# Schematic_V1.net
KiCad netlist of a schematic drawn in EAGLE
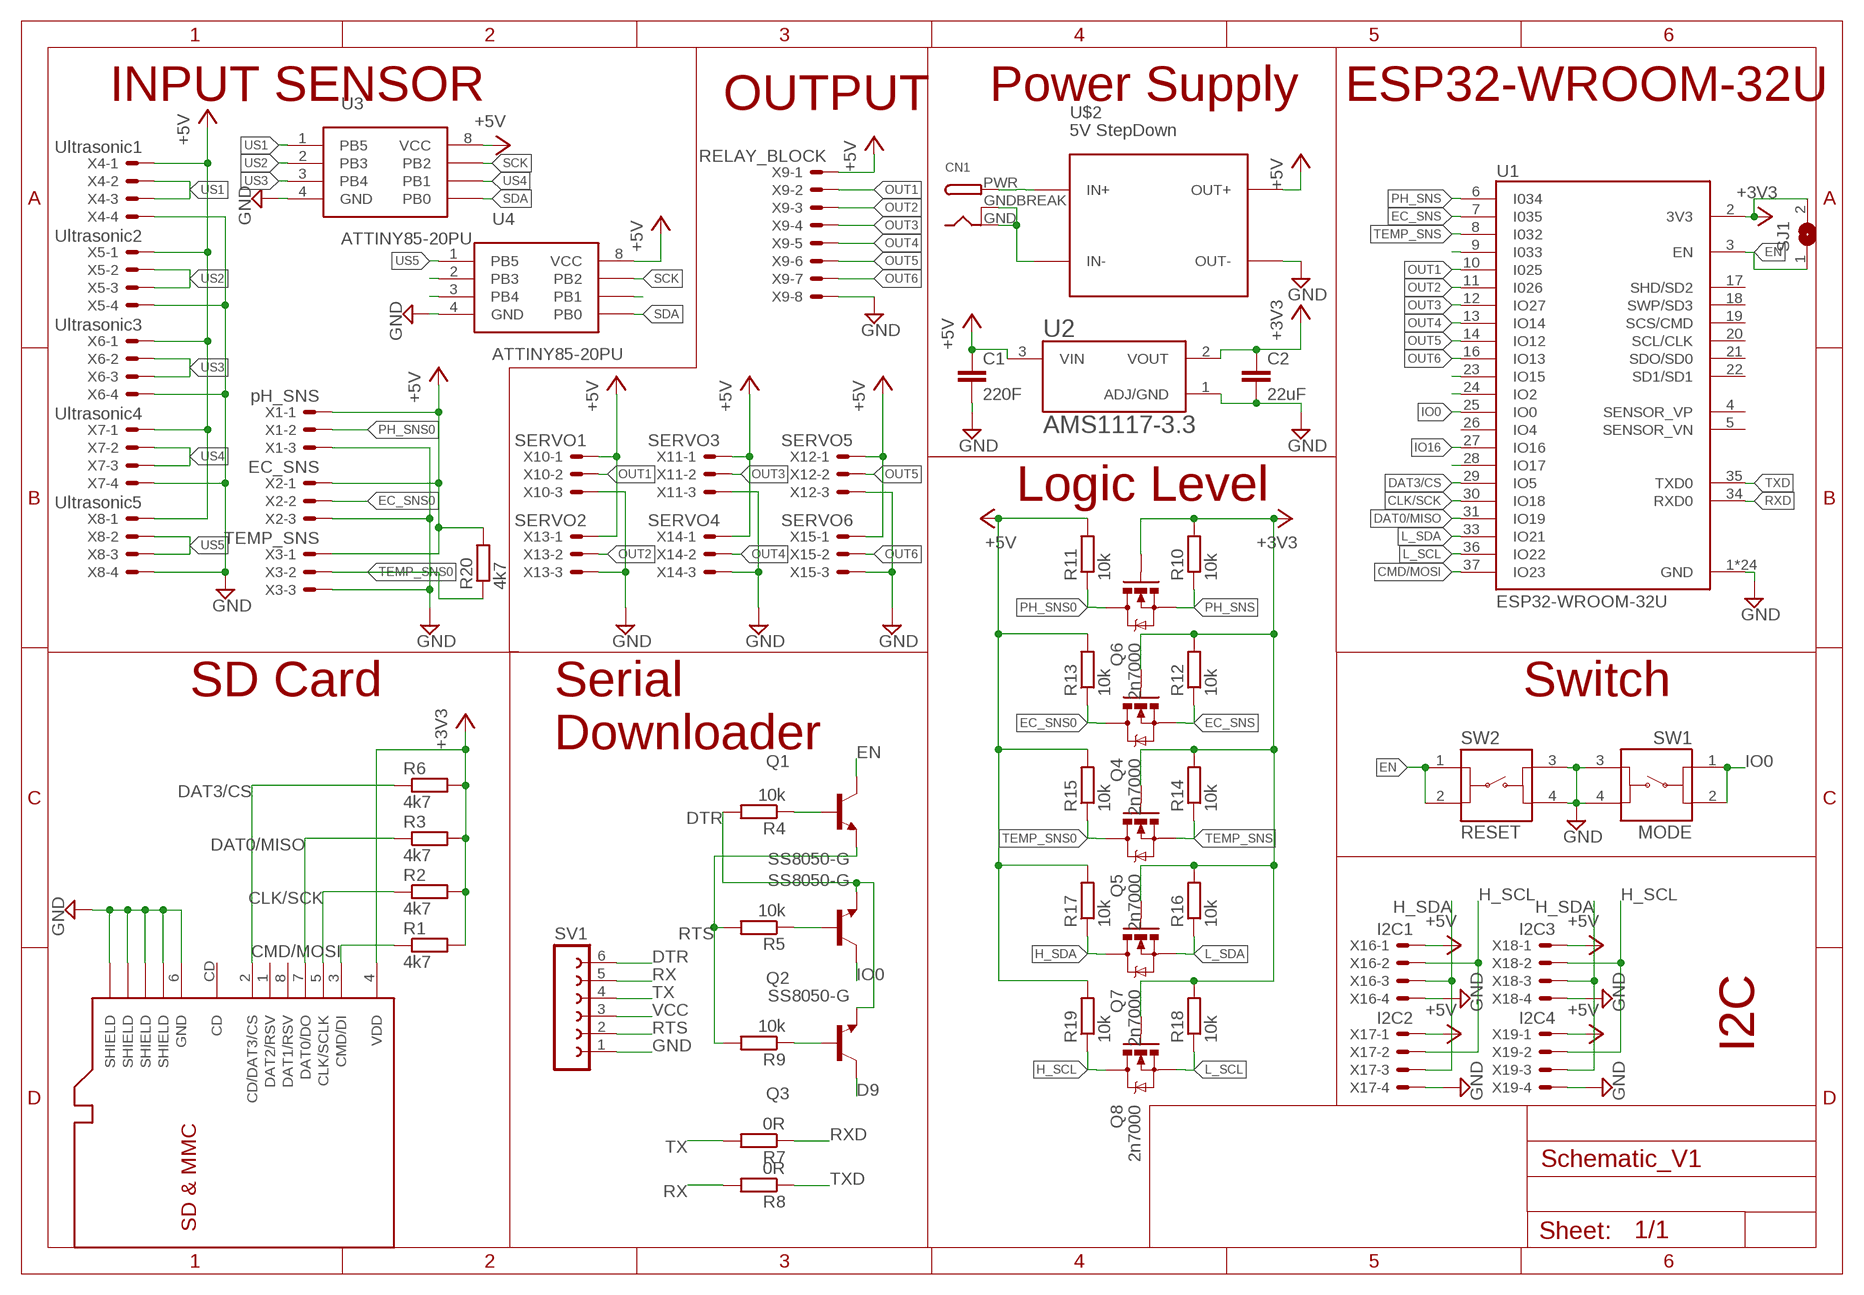
[diagram p0: schematic, sheet 1]

(export (version "E")
  (design (tool "Eeschema 10.0.6"))
  (components
    (comp (ref "C1")
      (value "220F")
      (footprint "eagle-import:C1206")
      (libsource (lib "eagle-import") (part "C-EUC1206"))
    )
    (comp (ref "C2")
      (value "22uF")
      (footprint "eagle-import:C1206")
      (libsource (lib "eagle-import") (part "C-EUC1206"))
    )
    (comp (ref "CN1")
      (value "DCBARRELPTH")
      (footprint "eagle-import:DCJACK_2MM_PTH")
      (libsource (lib "eagle-import") (part "DCBARRELPTH"))
    )
    (comp (ref "Q1")
      (value "SS8050-G")
      (footprint "eagle-import:SOT23")
      (fields
        (field (name "DIGIKEY_PART_NUMBER") "MMBT3904FSCT-ND")
        (field (name "MANUFACTURER") "ON Semiconductor")
        (field (name "MPN") "MMBT3904")
        (field (name "CREATED_BY") "PCBLayout.com")
      )
      (libsource (lib "eagle-import") (part "MMBT3904"))
    )
    (comp (ref "Q2")
      (value "SS8050-G")
      (footprint "eagle-import:SOT23")
      (fields
        (field (name "DIGIKEY_PART_NUMBER") "MMBT3904FSCT-ND")
        (field (name "MANUFACTURER") "ON Semiconductor")
        (field (name "MPN") "MMBT3904")
        (field (name "CREATED_BY") "PCBLayout.com")
      )
      (libsource (lib "eagle-import") (part "MMBT3904"))
    )
    (comp (ref "Q3")
      (value "SS8050-G")
      (footprint "eagle-import:SOT23")
      (fields
        (field (name "DIGIKEY_PART_NUMBER") "MMBT3904FSCT-ND")
        (field (name "MANUFACTURER") "ON Semiconductor")
        (field (name "MPN") "MMBT3904")
        (field (name "CREATED_BY") "PCBLayout.com")
      )
      (libsource (lib "eagle-import") (part "MMBT3904"))
    )
    (comp (ref "Q4")
      (value "2n7000")
      (footprint "eagle-import:SOT23")
      (libsource (lib "eagle-import") (part "MOSFET-NCHANNELBSS138"))
    )
    (comp (ref "Q5")
      (value "2n7000")
      (footprint "eagle-import:SOT23")
      (libsource (lib "eagle-import") (part "MOSFET-NCHANNELBSS138"))
    )
    (comp (ref "Q6")
      (value "2n7000")
      (footprint "eagle-import:SOT23")
      (libsource (lib "eagle-import") (part "MOSFET-NCHANNELBSS138"))
    )
    (comp (ref "Q7")
      (value "2n7000")
      (footprint "eagle-import:SOT23")
      (libsource (lib "eagle-import") (part "MOSFET-NCHANNELBSS138"))
    )
    (comp (ref "Q8")
      (value "2n7000")
      (footprint "eagle-import:SOT23")
      (libsource (lib "eagle-import") (part "MOSFET-NCHANNELBSS138"))
    )
    (comp (ref "R1")
      (value "4k7")
      (footprint "eagle-import:M1206")
      (libsource (lib "eagle-import") (part "R-EU_M1206"))
    )
    (comp (ref "R2")
      (value "4k7")
      (footprint "eagle-import:M1206")
      (libsource (lib "eagle-import") (part "R-EU_M1206"))
    )
    (comp (ref "R3")
      (value "4k7")
      (footprint "eagle-import:M1206")
      (libsource (lib "eagle-import") (part "R-EU_M1206"))
    )
    (comp (ref "R4")
      (value "10k")
      (footprint "eagle-import:M1206")
      (libsource (lib "eagle-import") (part "R-EU_M1206"))
    )
    (comp (ref "R5")
      (value "10k")
      (footprint "eagle-import:M1206")
      (libsource (lib "eagle-import") (part "R-EU_M1206"))
    )
    (comp (ref "R6")
      (value "4k7")
      (footprint "eagle-import:M1206")
      (libsource (lib "eagle-import") (part "R-EU_M1206"))
    )
    (comp (ref "R7")
      (value "0R")
      (footprint "eagle-import:M1206")
      (libsource (lib "eagle-import") (part "R-EU_M1206"))
    )
    (comp (ref "R8")
      (value "0R")
      (footprint "eagle-import:M1206")
      (libsource (lib "eagle-import") (part "R-EU_M1206"))
    )
    (comp (ref "R9")
      (value "10k")
      (footprint "eagle-import:M1206")
      (libsource (lib "eagle-import") (part "R-EU_M1206"))
    )
    (comp (ref "R10")
      (value "10k")
      (footprint "eagle-import:M1206")
      (libsource (lib "eagle-import") (part "R-EU_M1206"))
    )
    (comp (ref "R11")
      (value "10k")
      (footprint "eagle-import:M1206")
      (libsource (lib "eagle-import") (part "R-EU_M1206"))
    )
    (comp (ref "R12")
      (value "10k")
      (footprint "eagle-import:M1206")
      (libsource (lib "eagle-import") (part "R-EU_M1206"))
    )
    (comp (ref "R13")
      (value "10k")
      (footprint "eagle-import:M1206")
      (libsource (lib "eagle-import") (part "R-EU_M1206"))
    )
    (comp (ref "R14")
      (value "10k")
      (footprint "eagle-import:M1206")
      (libsource (lib "eagle-import") (part "R-EU_M1206"))
    )
    (comp (ref "R15")
      (value "10k")
      (footprint "eagle-import:M1206")
      (libsource (lib "eagle-import") (part "R-EU_M1206"))
    )
    (comp (ref "R16")
      (value "10k")
      (footprint "eagle-import:M1206")
      (libsource (lib "eagle-import") (part "R-EU_M1206"))
    )
    (comp (ref "R17")
      (value "10k")
      (footprint "eagle-import:M1206")
      (libsource (lib "eagle-import") (part "R-EU_M1206"))
    )
    (comp (ref "R18")
      (value "10k")
      (footprint "eagle-import:M1206")
      (libsource (lib "eagle-import") (part "R-EU_M1206"))
    )
    (comp (ref "R19")
      (value "10k")
      (footprint "eagle-import:M1206")
      (libsource (lib "eagle-import") (part "R-EU_M1206"))
    )
    (comp (ref "R20")
      (value "4k7")
      (footprint "eagle-import:M1206")
      (libsource (lib "eagle-import") (part "R-EU_M1206"))
    )
    (comp (ref "SJ1")
      (value "SJW")
      (footprint "eagle-import:SJW")
      (libsource (lib "eagle-import") (part "SJW"))
    )
    (comp (ref "SV1")
      (value "FE06-1")
      (footprint "eagle-import:FE06")
      (libsource (lib "eagle-import") (part "FE06-1"))
    )
    (comp (ref "SW1")
      (value "MODE")
      (footprint "eagle-import:1825910-6")
      (fields
        (field (name "DIGIKEY_PART_NUMBER") "450-1650-ND")
        (field (name "MANUFACTURER") "TE Connectivity ALCOSWITCH Switches")
        (field (name "MPN") "1825910-6")
        (field (name "CREATED_BY") " PCBLayout.com")
      )
      (libsource (lib "eagle-import") (part "1825910-6"))
    )
    (comp (ref "SW2")
      (value "RESET")
      (footprint "eagle-import:1825910-6")
      (fields
        (field (name "DIGIKEY_PART_NUMBER") "450-1650-ND")
        (field (name "MANUFACTURER") "TE Connectivity ALCOSWITCH Switches")
        (field (name "MPN") "1825910-6")
        (field (name "CREATED_BY") " PCBLayout.com")
      )
      (libsource (lib "eagle-import") (part "1825910-6"))
    )
    (comp (ref "U$1")
      (value "MICROSD")
      (footprint "eagle-import:C12075")
      (libsource (lib "eagle-import") (part "MICROSD"))
    )
    (comp (ref "U$2")
      (value "5V StepDown")
      (footprint "eagle-import:DC-DC-STEP-DOWN-LM2596")
      (libsource (lib "eagle-import") (part "DC-DC-STEP-DOWN-LM2596"))
    )
    (comp (ref "U1")
      (value "ESP32-WROOM-32U")
      (footprint "eagle-import:XCVR_ESP32-WROOM-32U")
      (fields (field (name "MF") "Espressif Systems"))
      (libsource (lib "eagle-import") (part "ESP32-WROOM-32U"))
    )
    (comp (ref "U2")
      (value "AMS1117-3.3")
      (footprint "eagle-import:SOT229P700X180-4N")
      (fields (field (name "MF") "Advanced Monolithic Systems"))
      (libsource (lib "eagle-import") (part "AMS1117-3.3"))
    )
    (comp (ref "U3")
      (value "ATTINY85-20PU")
      (footprint "eagle-import:PDIP-8")
      (fields
        (field (name "DIGI_KEY_PART_NUMBER") "ATTINY85-20PU-ND")
        (field (name "MANUFACTURER") "Microchip Technology")
        (field (name "CREATED_BY") "PCBLayout.com")
      )
      (libsource (lib "eagle-import") (part "ATTINY85-20PU"))
    )
    (comp (ref "U4")
      (value "ATTINY85-20PU")
      (footprint "eagle-import:PDIP-8")
      (fields
        (field (name "DIGI_KEY_PART_NUMBER") "ATTINY85-20PU-ND")
        (field (name "MANUFACTURER") "Microchip Technology")
        (field (name "CREATED_BY") "PCBLayout.com")
      )
      (libsource (lib "eagle-import") (part "ATTINY85-20PU"))
    )
    (comp (ref "X1")
      (value "pH_SNS")
      (footprint "eagle-import:JST-XH-03-PACKAGE-LONG-PAD")
      (libsource (lib "eagle-import") (part "JST-XH-03-PIN-LONG-PAD"))
    )
    (comp (ref "X2")
      (value "EC_SNS")
      (footprint "eagle-import:JST-XH-03-PACKAGE-LONG-PAD")
      (libsource (lib "eagle-import") (part "JST-XH-03-PIN-LONG-PAD"))
    )
    (comp (ref "X3")
      (value "TEMP_SNS")
      (footprint "eagle-import:JST-XH-03-PACKAGE-LONG-PAD")
      (libsource (lib "eagle-import") (part "JST-XH-03-PIN-LONG-PAD"))
    )
    (comp (ref "X4")
      (value "Ultrasonic1")
      (footprint "eagle-import:JST-XH-04-PACKAGE-LONG-PAD")
      (libsource (lib "eagle-import") (part "JST-XH-04-PIN-LONG-PAD"))
    )
    (comp (ref "X5")
      (value "Ultrasonic2")
      (footprint "eagle-import:JST-XH-04-PACKAGE-LONG-PAD")
      (libsource (lib "eagle-import") (part "JST-XH-04-PIN-LONG-PAD"))
    )
    (comp (ref "X6")
      (value "Ultrasonic3")
      (footprint "eagle-import:JST-XH-04-PACKAGE-LONG-PAD")
      (libsource (lib "eagle-import") (part "JST-XH-04-PIN-LONG-PAD"))
    )
    (comp (ref "X7")
      (value "Ultrasonic4")
      (footprint "eagle-import:JST-XH-04-PACKAGE-LONG-PAD")
      (libsource (lib "eagle-import") (part "JST-XH-04-PIN-LONG-PAD"))
    )
    (comp (ref "X8")
      (value "Ultrasonic5")
      (footprint "eagle-import:JST-XH-04-PACKAGE-LONG-PAD")
      (libsource (lib "eagle-import") (part "JST-XH-04-PIN-LONG-PAD"))
    )
    (comp (ref "X9")
      (value "RELAY_BLOCK")
      (footprint "eagle-import:JST-XH-08-PACKAGE-LONG-PAD")
      (libsource (lib "eagle-import") (part "JST-XH-08-PIN-LONG-PAD"))
    )
    (comp (ref "X10")
      (value "SERVO1")
      (footprint "eagle-import:JST-XH-03-PACKAGE-LONG-PAD")
      (libsource (lib "eagle-import") (part "JST-XH-03-PIN-LONG-PAD"))
    )
    (comp (ref "X11")
      (value "SERVO3")
      (footprint "eagle-import:JST-XH-03-PACKAGE-LONG-PAD")
      (libsource (lib "eagle-import") (part "JST-XH-03-PIN-LONG-PAD"))
    )
    (comp (ref "X12")
      (value "SERVO5")
      (footprint "eagle-import:JST-XH-03-PACKAGE-LONG-PAD")
      (libsource (lib "eagle-import") (part "JST-XH-03-PIN-LONG-PAD"))
    )
    (comp (ref "X13")
      (value "SERVO2")
      (footprint "eagle-import:JST-XH-03-PACKAGE-LONG-PAD")
      (libsource (lib "eagle-import") (part "JST-XH-03-PIN-LONG-PAD"))
    )
    (comp (ref "X14")
      (value "SERVO4")
      (footprint "eagle-import:JST-XH-03-PACKAGE-LONG-PAD")
      (libsource (lib "eagle-import") (part "JST-XH-03-PIN-LONG-PAD"))
    )
    (comp (ref "X15")
      (value "SERVO6")
      (footprint "eagle-import:JST-XH-03-PACKAGE-LONG-PAD")
      (libsource (lib "eagle-import") (part "JST-XH-03-PIN-LONG-PAD"))
    )
    (comp (ref "X16")
      (value "I2C1")
      (footprint "eagle-import:JST-XH-04-PACKAGE-LONG-PAD")
      (libsource (lib "eagle-import") (part "JST-XH-04-PIN-LONG-PAD"))
    )
    (comp (ref "X17")
      (value "I2C2")
      (footprint "eagle-import:JST-XH-04-PACKAGE-LONG-PAD")
      (libsource (lib "eagle-import") (part "JST-XH-04-PIN-LONG-PAD"))
    )
    (comp (ref "X18")
      (value "I2C3")
      (footprint "eagle-import:JST-XH-04-PACKAGE-LONG-PAD")
      (libsource (lib "eagle-import") (part "JST-XH-04-PIN-LONG-PAD"))
    )
    (comp (ref "X19")
      (value "I2C4")
      (footprint "eagle-import:JST-XH-04-PACKAGE-LONG-PAD")
      (libsource (lib "eagle-import") (part "JST-XH-04-PIN-LONG-PAD"))
    )
  )
  (nets
    (net (code "1") (name "+3V3") (class "Default")
      (node (ref "C2") (pin "1") (pinfunction "1_1") (pintype "passive"))
      (node (ref "Q4") (pin "1") (pinfunction "G_1") (pintype "passive"))
      (node (ref "Q5") (pin "1") (pinfunction "G_1") (pintype "passive"))
      (node (ref "Q6") (pin "1") (pinfunction "G_1") (pintype "passive"))
      (node (ref "Q7") (pin "1") (pinfunction "G_1") (pintype "passive"))
      (node (ref "Q8") (pin "1") (pinfunction "G_1") (pintype "passive"))
      (node (ref "R1") (pin "2") (pinfunction "2_2") (pintype "passive"))
      (node (ref "R10") (pin "2") (pinfunction "2_2") (pintype "passive"))
      (node (ref "R12") (pin "2") (pinfunction "2_2") (pintype "passive"))
      (node (ref "R14") (pin "2") (pinfunction "2_2") (pintype "passive"))
      (node (ref "R16") (pin "2") (pinfunction "2_2") (pintype "passive"))
      (node (ref "R18") (pin "2") (pinfunction "2_2") (pintype "passive"))
      (node (ref "R2") (pin "2") (pinfunction "2_2") (pintype "passive"))
      (node (ref "R3") (pin "2") (pinfunction "2_2") (pintype "passive"))
      (node (ref "R6") (pin "2") (pinfunction "2_2") (pintype "passive"))
      (node (ref "SJ1") (pin "2") (pinfunction "2_2") (pintype "passive"))
      (node (ref "U$1") (pin "4") (pinfunction "VDD_4") (pintype "power_in"))
      (node (ref "U1") (pin "2") (pinfunction "3V3_2") (pintype "power_in"))
      (node (ref "U2") (pin "2") (pinfunction "VOUT_2") (pintype "output"))
    )
    (net (code "2") (name "+5V") (class "Default")
      (node (ref "C1") (pin "1") (pinfunction "1_1") (pintype "passive"))
      (node (ref "R11") (pin "2") (pinfunction "2_2") (pintype "passive"))
      (node (ref "R13") (pin "2") (pinfunction "2_2") (pintype "passive"))
      (node (ref "R15") (pin "2") (pinfunction "2_2") (pintype "passive"))
      (node (ref "R17") (pin "2") (pinfunction "2_2") (pintype "passive"))
      (node (ref "R19") (pin "2") (pinfunction "2_2") (pintype "passive"))
      (node (ref "R20") (pin "2") (pinfunction "2_2") (pintype "passive"))
      (node (ref "U$2") (pin "OUT+") (pinfunction "OUT+_OUT+") (pintype "bidirectional"))
      (node (ref "U2") (pin "3") (pinfunction "VIN_3") (pintype "input"))
      (node (ref "U3") (pin "8") (pinfunction "VCC_8") (pintype "power_in"))
      (node (ref "U4") (pin "8") (pinfunction "VCC_8") (pintype "power_in"))
      (node (ref "X1") (pin "1") (pinfunction "S_1") (pintype "passive"))
      (node (ref "X10") (pin "1") (pinfunction "S_1") (pintype "passive"))
      (node (ref "X11") (pin "1") (pinfunction "S_1") (pintype "passive"))
      (node (ref "X12") (pin "1") (pinfunction "S_1") (pintype "passive"))
      (node (ref "X13") (pin "1") (pinfunction "S_1") (pintype "passive"))
      (node (ref "X14") (pin "1") (pinfunction "S_1") (pintype "passive"))
      (node (ref "X15") (pin "1") (pinfunction "S_1") (pintype "passive"))
      (node (ref "X16") (pin "1") (pinfunction "S_1") (pintype "passive"))
      (node (ref "X17") (pin "1") (pinfunction "S_1") (pintype "passive"))
      (node (ref "X18") (pin "1") (pinfunction "S_1") (pintype "passive"))
      (node (ref "X19") (pin "1") (pinfunction "S_1") (pintype "passive"))
      (node (ref "X2") (pin "1") (pinfunction "S_1") (pintype "passive"))
      (node (ref "X3") (pin "1") (pinfunction "S_1") (pintype "passive"))
      (node (ref "X4") (pin "1") (pinfunction "S_1") (pintype "passive"))
      (node (ref "X5") (pin "1") (pinfunction "S_1") (pintype "passive"))
      (node (ref "X6") (pin "1") (pinfunction "S_1") (pintype "passive"))
      (node (ref "X7") (pin "1") (pinfunction "S_1") (pintype "passive"))
      (node (ref "X8") (pin "1") (pinfunction "S_1") (pintype "passive"))
      (node (ref "X9") (pin "1") (pinfunction "S_1") (pintype "passive"))
    )
    (net (code "3") (name "/D9") (class "Default")
      (node (ref "Q3") (pin "3") (pinfunction "C_3") (pintype "passive"))
    )
    (net (code "4") (name "/DTR") (class "Default")
      (node (ref "Q2") (pin "2") (pinfunction "E_2") (pintype "passive"))
      (node (ref "Q3") (pin "2") (pinfunction "E_2") (pintype "passive"))
      (node (ref "R4") (pin "2") (pinfunction "2_2") (pintype "passive"))
      (node (ref "SV1") (pin "6") (pinfunction "6_6") (pintype "passive"))
    )
    (net (code "5") (name "/RTS") (class "Default")
      (node (ref "Q1") (pin "2") (pinfunction "E_2") (pintype "passive"))
      (node (ref "R5") (pin "2") (pinfunction "2_2") (pintype "passive"))
      (node (ref "R9") (pin "2") (pinfunction "2_2") (pintype "passive"))
      (node (ref "SV1") (pin "2") (pinfunction "2_2") (pintype "passive"))
    )
    (net (code "6") (name "/RX") (class "Default")
      (node (ref "R8") (pin "2") (pinfunction "2_2") (pintype "passive"))
      (node (ref "SV1") (pin "5") (pinfunction "5_5") (pintype "passive"))
    )
    (net (code "7") (name "/TX") (class "Default")
      (node (ref "R7") (pin "2") (pinfunction "2_2") (pintype "passive"))
      (node (ref "SV1") (pin "4") (pinfunction "4_4") (pintype "passive"))
    )
    (net (code "8") (name "/VCC") (class "Default")
      (node (ref "SV1") (pin "3") (pinfunction "3_3") (pintype "passive"))
    )
    (net (code "9") (name "CLK{slash}SCK") (class "Default")
      (node (ref "R2") (pin "1") (pinfunction "1_1") (pintype "passive"))
      (node (ref "U$1") (pin "5") (pinfunction "CLK/SCLK_5") (pintype "bidirectional"))
      (node (ref "U1") (pin "30") (pinfunction "IO18_30") (pintype "bidirectional"))
    )
    (net (code "10") (name "CMD{slash}MOSI") (class "Default")
      (node (ref "R1") (pin "1") (pinfunction "1_1") (pintype "passive"))
      (node (ref "U$1") (pin "3") (pinfunction "CMD/DI_3") (pintype "bidirectional"))
      (node (ref "U1") (pin "23") (pinfunction "IO15_23") (pintype "bidirectional"))
      (node (ref "U1") (pin "37") (pinfunction "IO23_37") (pintype "bidirectional"))
    )
    (net (code "11") (name "DAT0{slash}MISO") (class "Default")
      (node (ref "R3") (pin "1") (pinfunction "1_1") (pintype "passive"))
      (node (ref "U$1") (pin "7") (pinfunction "DAT0/DO_7") (pintype "bidirectional"))
      (node (ref "U1") (pin "31") (pinfunction "IO19_31") (pintype "bidirectional"))
    )
    (net (code "12") (name "DAT3{slash}CS") (class "Default")
      (node (ref "R6") (pin "1") (pinfunction "1_1") (pintype "passive"))
      (node (ref "U$1") (pin "2") (pinfunction "CD/DAT3/CS_2") (pintype "bidirectional"))
      (node (ref "U1") (pin "29") (pinfunction "IO5_29") (pintype "bidirectional"))
    )
    (net (code "13") (name "EC_SNS") (class "Default")
      (node (ref "Q4") (pin "2") (pinfunction "S_2") (pintype "passive"))
      (node (ref "R12") (pin "1") (pinfunction "1_1") (pintype "passive"))
      (node (ref "U1") (pin "7") (pinfunction "I035_7") (pintype "input"))
    )
    (net (code "14") (name "EC_SNS0") (class "Default")
      (node (ref "Q4") (pin "3") (pinfunction "D_3") (pintype "passive"))
      (node (ref "R13") (pin "1") (pinfunction "1_1") (pintype "passive"))
      (node (ref "X2") (pin "2") (pinfunction "S_2") (pintype "passive"))
    )
    (net (code "15") (name "EN") (class "Default")
      (node (ref "Q1") (pin "3") (pinfunction "C_3") (pintype "passive"))
      (node (ref "SJ1") (pin "1") (pinfunction "1_1") (pintype "passive"))
      (node (ref "SW2") (pin "1") (pinfunction "1_1") (pintype "passive"))
      (node (ref "SW2") (pin "2") (pinfunction "2_2") (pintype "passive"))
      (node (ref "U1") (pin "3") (pinfunction "EN_3") (pintype "input"))
    )
    (net (code "16") (name "GND") (class "Default")
      (node (ref "C1") (pin "2") (pinfunction "2_2") (pintype "passive"))
      (node (ref "C2") (pin "2") (pinfunction "2_2") (pintype "passive"))
      (node (ref "SV1") (pin "1") (pinfunction "1_1") (pintype "passive"))
      (node (ref "SW1") (pin "3") (pinfunction "3_3") (pintype "passive"))
      (node (ref "SW1") (pin "4") (pinfunction "4_4") (pintype "passive"))
      (node (ref "SW2") (pin "3") (pinfunction "3_3") (pintype "passive"))
      (node (ref "SW2") (pin "4") (pinfunction "4_4") (pintype "passive"))
      (node (ref "U$1") (pin "6") (pinfunction "GND_6") (pintype "power_in"))
      (node (ref "U$1") (pin "GND@1") (pinfunction "SHIELD_GND@1") (pintype "power_in"))
      (node (ref "U$1") (pin "GND@2") (pinfunction "SHIELD_GND@2") (pintype "power_in"))
      (node (ref "U$1") (pin "GND@3") (pinfunction "SHIELD_GND@3") (pintype "power_in"))
      (node (ref "U$1") (pin "GND@4") (pinfunction "SHIELD_GND@4") (pintype "power_in"))
      (node (ref "U$2") (pin "OUT-") (pinfunction "OUT-_OUT-") (pintype "bidirectional"))
      (node (ref "U1") (pin "1") (pinfunction "GND_1") (pintype "power_in"))
      (node (ref "U1") (pin "15") (pinfunction "GND_15") (pintype "power_in"))
      (node (ref "U1") (pin "38") (pinfunction "GND_38") (pintype "power_in"))
      (node (ref "U1") (pin "G.1") (pinfunction "GND_G.1") (pintype "power_in"))
      (node (ref "U1") (pin "G.10") (pinfunction "GND_G.10") (pintype "power_in"))
      (node (ref "U1") (pin "G.11") (pinfunction "GND_G.11") (pintype "power_in"))
      (node (ref "U1") (pin "G.12") (pinfunction "GND_G.12") (pintype "power_in"))
      (node (ref "U1") (pin "G.13") (pinfunction "GND_G.13") (pintype "power_in"))
      (node (ref "U1") (pin "G.14") (pinfunction "GND_G.14") (pintype "power_in"))
      (node (ref "U1") (pin "G.15") (pinfunction "GND_G.15") (pintype "power_in"))
      (node (ref "U1") (pin "G.16") (pinfunction "GND_G.16") (pintype "power_in"))
      (node (ref "U1") (pin "G.17") (pinfunction "GND_G.17") (pintype "power_in"))
      (node (ref "U1") (pin "G.18") (pinfunction "GND_G.18") (pintype "power_in"))
      (node (ref "U1") (pin "G.19") (pinfunction "GND_G.19") (pintype "power_in"))
      (node (ref "U1") (pin "G.2") (pinfunction "GND_G.2") (pintype "power_in"))
      (node (ref "U1") (pin "G.20") (pinfunction "GND_G.20") (pintype "power_in"))
      (node (ref "U1") (pin "G.21") (pinfunction "GND_G.21") (pintype "power_in"))
      (node (ref "U1") (pin "G.22") (pinfunction "GND_G.22") (pintype "power_in"))
      (node (ref "U1") (pin "G.4") (pinfunction "GND_G.4") (pintype "power_in"))
      (node (ref "U1") (pin "G.5") (pinfunction "GND_G.5") (pintype "power_in"))
      (node (ref "U1") (pin "G.6") (pinfunction "GND_G.6") (pintype "power_in"))
      (node (ref "U1") (pin "G.7") (pinfunction "GND_G.7") (pintype "power_in"))
      (node (ref "U1") (pin "G.8") (pinfunction "GND_G.8") (pintype "power_in"))
      (node (ref "U1") (pin "G.9") (pinfunction "GND_G.9") (pintype "power_in"))
      (node (ref "U2") (pin "1") (pinfunction "ADJ/GND_1") (pintype "power_in"))
      (node (ref "U3") (pin "4") (pinfunction "GND_4") (pintype "power_in"))
      (node (ref "U4") (pin "4") (pinfunction "GND_4") (pintype "power_in"))
      (node (ref "X1") (pin "3") (pinfunction "S_3") (pintype "passive"))
      (node (ref "X10") (pin "3") (pinfunction "S_3") (pintype "passive"))
      (node (ref "X11") (pin "3") (pinfunction "S_3") (pintype "passive"))
      (node (ref "X12") (pin "3") (pinfunction "S_3") (pintype "passive"))
      (node (ref "X13") (pin "3") (pinfunction "S_3") (pintype "passive"))
      (node (ref "X14") (pin "3") (pinfunction "S_3") (pintype "passive"))
      (node (ref "X15") (pin "3") (pinfunction "S_3") (pintype "passive"))
      (node (ref "X16") (pin "4") (pinfunction "S_4") (pintype "passive"))
      (node (ref "X17") (pin "4") (pinfunction "S_4") (pintype "passive"))
      (node (ref "X18") (pin "4") (pinfunction "S_4") (pintype "passive"))
      (node (ref "X19") (pin "4") (pinfunction "S_4") (pintype "passive"))
      (node (ref "X2") (pin "3") (pinfunction "S_3") (pintype "passive"))
      (node (ref "X3") (pin "3") (pinfunction "S_3") (pintype "passive"))
      (node (ref "X4") (pin "4") (pinfunction "S_4") (pintype "passive"))
      (node (ref "X5") (pin "4") (pinfunction "S_4") (pintype "passive"))
      (node (ref "X6") (pin "4") (pinfunction "S_4") (pintype "passive"))
      (node (ref "X7") (pin "4") (pinfunction "S_4") (pintype "passive"))
      (node (ref "X8") (pin "4") (pinfunction "S_4") (pintype "passive"))
      (node (ref "X9") (pin "8") (pinfunction "S_8") (pintype "passive"))
    )
    (net (code "17") (name "H_SCL") (class "Default")
      (node (ref "Q8") (pin "3") (pinfunction "D_3") (pintype "passive"))
      (node (ref "R19") (pin "1") (pinfunction "1_1") (pintype "passive"))
      (node (ref "X16") (pin "2") (pinfunction "S_2") (pintype "passive"))
      (node (ref "X17") (pin "2") (pinfunction "S_2") (pintype "passive"))
      (node (ref "X18") (pin "2") (pinfunction "S_2") (pintype "passive"))
      (node (ref "X19") (pin "2") (pinfunction "S_2") (pintype "passive"))
    )
    (net (code "18") (name "H_SDA") (class "Default")
      (node (ref "Q7") (pin "3") (pinfunction "D_3") (pintype "passive"))
      (node (ref "R17") (pin "1") (pinfunction "1_1") (pintype "passive"))
      (node (ref "X16") (pin "3") (pinfunction "S_3") (pintype "passive"))
      (node (ref "X17") (pin "3") (pinfunction "S_3") (pintype "passive"))
      (node (ref "X18") (pin "3") (pinfunction "S_3") (pintype "passive"))
      (node (ref "X19") (pin "3") (pinfunction "S_3") (pintype "passive"))
    )
    (net (code "19") (name "IO0") (class "Default")
      (node (ref "Q2") (pin "3") (pinfunction "C_3") (pintype "passive"))
      (node (ref "SW1") (pin "1") (pinfunction "1_1") (pintype "passive"))
      (node (ref "SW1") (pin "2") (pinfunction "2_2") (pintype "passive"))
      (node (ref "U1") (pin "25") (pinfunction "IO0_25") (pintype "bidirectional"))
    )
    (net (code "20") (name "IO16") (class "Default")
      (node (ref "U1") (pin "27") (pinfunction "IO16_27") (pintype "bidirectional"))
    )
    (net (code "21") (name "L_SCL") (class "Default")
      (node (ref "Q8") (pin "2") (pinfunction "S_2") (pintype "passive"))
      (node (ref "R18") (pin "1") (pinfunction "1_1") (pintype "passive"))
      (node (ref "U1") (pin "36") (pinfunction "IO22_36") (pintype "bidirectional"))
    )
    (net (code "22") (name "L_SDA") (class "Default")
      (node (ref "Q7") (pin "2") (pinfunction "S_2") (pintype "passive"))
      (node (ref "R16") (pin "1") (pinfunction "1_1") (pintype "passive"))
      (node (ref "U1") (pin "33") (pinfunction "IO21_33") (pintype "bidirectional"))
    )
    (net (code "23") (name "Net-(CN1-PadGND)") (class "Default")
      (node (ref "CN1") (pin "GND") (pinfunction "GND_GND") (pintype "power_in"))
      (node (ref "CN1") (pin "GNDBREAK") (pinfunction "GNDBREAK_GNDBREAK") (pintype "power_in"))
      (node (ref "U$2") (pin "IN-") (pinfunction "IN-_IN-") (pintype "bidirectional"))
    )
    (net (code "24") (name "Net-(CN1-PadPWR)") (class "Default")
      (node (ref "CN1") (pin "PWR") (pinfunction "PWR_PWR") (pintype "power_in"))
      (node (ref "U$2") (pin "IN+") (pinfunction "IN+_IN+") (pintype "bidirectional"))
    )
    (net (code "25") (name "Net-(Q1-B)") (class "Default")
      (node (ref "Q1") (pin "1") (pinfunction "B_1") (pintype "passive"))
      (node (ref "R4") (pin "1") (pinfunction "1_1") (pintype "passive"))
    )
    (net (code "26") (name "Net-(Q2-B)") (class "Default")
      (node (ref "Q2") (pin "1") (pinfunction "B_1") (pintype "passive"))
      (node (ref "R5") (pin "1") (pinfunction "1_1") (pintype "passive"))
    )
    (net (code "27") (name "Net-(Q3-B)") (class "Default")
      (node (ref "Q3") (pin "1") (pinfunction "B_1") (pintype "passive"))
      (node (ref "R9") (pin "1") (pinfunction "1_1") (pintype "passive"))
    )
    (net (code "28") (name "OUT1") (class "Default")
      (node (ref "U1") (pin "10") (pinfunction "I025_10") (pintype "bidirectional"))
      (node (ref "X10") (pin "2") (pinfunction "S_2") (pintype "passive"))
      (node (ref "X9") (pin "2") (pinfunction "S_2") (pintype "passive"))
    )
    (net (code "29") (name "OUT2") (class "Default")
      (node (ref "U1") (pin "11") (pinfunction "I026_11") (pintype "bidirectional"))
      (node (ref "X13") (pin "2") (pinfunction "S_2") (pintype "passive"))
      (node (ref "X9") (pin "3") (pinfunction "S_3") (pintype "passive"))
    )
    (net (code "30") (name "OUT3") (class "Default")
      (node (ref "U1") (pin "12") (pinfunction "IO27_12") (pintype "bidirectional"))
      (node (ref "X11") (pin "2") (pinfunction "S_2") (pintype "passive"))
      (node (ref "X9") (pin "4") (pinfunction "S_4") (pintype "passive"))
    )
    (net (code "31") (name "OUT4") (class "Default")
      (node (ref "U1") (pin "13") (pinfunction "IO14_13") (pintype "bidirectional"))
      (node (ref "X14") (pin "2") (pinfunction "S_2") (pintype "passive"))
      (node (ref "X9") (pin "5") (pinfunction "S_5") (pintype "passive"))
    )
    (net (code "32") (name "OUT5") (class "Default")
      (node (ref "U1") (pin "14") (pinfunction "IO12_14") (pintype "bidirectional"))
      (node (ref "X12") (pin "2") (pinfunction "S_2") (pintype "passive"))
      (node (ref "X9") (pin "6") (pinfunction "S_6") (pintype "passive"))
    )
    (net (code "33") (name "OUT6") (class "Default")
      (node (ref "U1") (pin "16") (pinfunction "IO13_16") (pintype "bidirectional"))
      (node (ref "X15") (pin "2") (pinfunction "S_2") (pintype "passive"))
      (node (ref "X9") (pin "7") (pinfunction "S_7") (pintype "passive"))
    )
    (net (code "34") (name "PH_SNS") (class "Default")
      (node (ref "Q6") (pin "2") (pinfunction "S_2") (pintype "passive"))
      (node (ref "R10") (pin "1") (pinfunction "1_1") (pintype "passive"))
      (node (ref "U1") (pin "6") (pinfunction "I034_6") (pintype "input"))
    )
    (net (code "35") (name "PH_SNS0") (class "Default")
      (node (ref "Q6") (pin "3") (pinfunction "D_3") (pintype "passive"))
      (node (ref "R11") (pin "1") (pinfunction "1_1") (pintype "passive"))
      (node (ref "X1") (pin "2") (pinfunction "S_2") (pintype "passive"))
    )
    (net (code "36") (name "RXD") (class "Default")
      (node (ref "R7") (pin "1") (pinfunction "1_1") (pintype "passive"))
      (node (ref "U1") (pin "34") (pinfunction "RXD0_34") (pintype "bidirectional"))
    )
    (net (code "37") (name "SCK") (class "Default")
      (node (ref "U3") (pin "7") (pinfunction "PB2_7") (pintype "bidirectional"))
      (node (ref "U4") (pin "7") (pinfunction "PB2_7") (pintype "bidirectional"))
    )
    (net (code "38") (name "SDA") (class "Default")
      (node (ref "U3") (pin "5") (pinfunction "PB0_5") (pintype "bidirectional"))
      (node (ref "U4") (pin "5") (pinfunction "PB0_5") (pintype "bidirectional"))
    )
    (net (code "39") (name "TEMP_SNS") (class "Default")
      (node (ref "Q5") (pin "2") (pinfunction "S_2") (pintype "passive"))
      (node (ref "R14") (pin "1") (pinfunction "1_1") (pintype "passive"))
      (node (ref "U1") (pin "8") (pinfunction "I032_8") (pintype "bidirectional"))
    )
    (net (code "40") (name "TEMP_SNS0") (class "Default")
      (node (ref "Q5") (pin "3") (pinfunction "D_3") (pintype "passive"))
      (node (ref "R15") (pin "1") (pinfunction "1_1") (pintype "passive"))
      (node (ref "R20") (pin "1") (pinfunction "1_1") (pintype "passive"))
      (node (ref "X3") (pin "2") (pinfunction "S_2") (pintype "passive"))
    )
    (net (code "41") (name "TXD") (class "Default")
      (node (ref "R8") (pin "1") (pinfunction "1_1") (pintype "passive"))
      (node (ref "U1") (pin "35") (pinfunction "TXD0_35") (pintype "bidirectional"))
    )
    (net (code "42") (name "US1") (class "Default")
      (node (ref "U3") (pin "1") (pinfunction "PB5_1") (pintype "bidirectional"))
      (node (ref "X4") (pin "2") (pinfunction "S_2") (pintype "passive"))
      (node (ref "X4") (pin "3") (pinfunction "S_3") (pintype "passive"))
    )
    (net (code "43") (name "US2") (class "Default")
      (node (ref "U3") (pin "2") (pinfunction "PB3_2") (pintype "bidirectional"))
      (node (ref "X5") (pin "2") (pinfunction "S_2") (pintype "passive"))
      (node (ref "X5") (pin "3") (pinfunction "S_3") (pintype "passive"))
    )
    (net (code "44") (name "US3") (class "Default")
      (node (ref "U3") (pin "3") (pinfunction "PB4_3") (pintype "bidirectional"))
      (node (ref "X6") (pin "2") (pinfunction "S_2") (pintype "passive"))
      (node (ref "X6") (pin "3") (pinfunction "S_3") (pintype "passive"))
    )
    (net (code "45") (name "US4") (class "Default")
      (node (ref "U3") (pin "6") (pinfunction "PB1_6") (pintype "bidirectional"))
      (node (ref "X7") (pin "2") (pinfunction "S_2") (pintype "passive"))
      (node (ref "X7") (pin "3") (pinfunction "S_3") (pintype "passive"))
    )
    (net (code "46") (name "US5") (class "Default")
      (node (ref "U4") (pin "1") (pinfunction "PB5_1") (pintype "bidirectional"))
      (node (ref "X8") (pin "2") (pinfunction "S_2") (pintype "passive"))
      (node (ref "X8") (pin "3") (pinfunction "S_3") (pintype "passive"))
    )
    (net (code "47") (name "unconnected-(U$1-DAT1{slash}RSV-Pad8)") (class "Default")
      (node (ref "U$1") (pin "8") (pinfunction "DAT1/RSV_8") (pintype "bidirectional"))
    )
    (net (code "48") (name "unconnected-(U$1-DAT2{slash}RSV-Pad1)") (class "Default")
      (node (ref "U$1") (pin "1") (pinfunction "DAT2/RSV_1") (pintype "bidirectional"))
    )
    (net (code "49") (name "unconnected-(U$1-PadCD)") (class "Default")
      (node (ref "U$1") (pin "CD") (pinfunction "CD_CD") (pintype "bidirectional"))
    )
    (net (code "50") (name "unconnected-(U1-I033-Pad9)") (class "Default")
      (node (ref "U1") (pin "9") (pinfunction "I033_9") (pintype "bidirectional"))
    )
    (net (code "51") (name "unconnected-(U1-IO2-Pad24)") (class "Default")
      (node (ref "U1") (pin "24") (pinfunction "IO2_24") (pintype "bidirectional"))
    )
    (net (code "52") (name "unconnected-(U1-IO4-Pad26)") (class "Default")
      (node (ref "U1") (pin "26") (pinfunction "IO4_26") (pintype "bidirectional"))
    )
    (net (code "53") (name "unconnected-(U1-IO17-Pad28)") (class "Default")
      (node (ref "U1") (pin "28") (pinfunction "IO17_28") (pintype "bidirectional"))
    )
    (net (code "54") (name "unconnected-(U1-SCL{slash}CLK-Pad20)") (class "Default")
      (node (ref "U1") (pin "20") (pinfunction "SCL/CLK_20") (pintype "bidirectional"))
    )
    (net (code "55") (name "unconnected-(U1-SCS{slash}CMD-Pad19)") (class "Default")
      (node (ref "U1") (pin "19") (pinfunction "SCS/CMD_19") (pintype "bidirectional"))
    )
    (net (code "56") (name "unconnected-(U1-SD1{slash}SD1-Pad22)") (class "Default")
      (node (ref "U1") (pin "22") (pinfunction "SD1/SD1_22") (pintype "bidirectional"))
    )
    (net (code "57") (name "unconnected-(U1-SDO{slash}SD0-Pad21)") (class "Default")
      (node (ref "U1") (pin "21") (pinfunction "SDO/SD0_21") (pintype "bidirectional"))
    )
    (net (code "58") (name "unconnected-(U1-SENSOR_VN-Pad5)") (class "Default")
      (node (ref "U1") (pin "5") (pinfunction "SENSOR_VN_5") (pintype "input"))
    )
    (net (code "59") (name "unconnected-(U1-SENSOR_VP-Pad4)") (class "Default")
      (node (ref "U1") (pin "4") (pinfunction "SENSOR_VP_4") (pintype "input"))
    )
    (net (code "60") (name "unconnected-(U1-SHD{slash}SD2-Pad17)") (class "Default")
      (node (ref "U1") (pin "17") (pinfunction "SHD/SD2_17") (pintype "bidirectional"))
    )
    (net (code "61") (name "unconnected-(U1-SWP{slash}SD3-Pad18)") (class "Default")
      (node (ref "U1") (pin "18") (pinfunction "SWP/SD3_18") (pintype "bidirectional"))
    )
    (net (code "62") (name "unconnected-(U4-PB1-Pad6)") (class "Default")
      (node (ref "U4") (pin "6") (pinfunction "PB1_6") (pintype "bidirectional"))
    )
    (net (code "63") (name "unconnected-(U4-PB3-Pad2)") (class "Default")
      (node (ref "U4") (pin "2") (pinfunction "PB3_2") (pintype "bidirectional"))
    )
    (net (code "64") (name "unconnected-(U4-PB4-Pad3)") (class "Default")
      (node (ref "U4") (pin "3") (pinfunction "PB4_3") (pintype "bidirectional"))
    )
  )
)
